# FLC100_remote_v2.net
KiCad netlist of a schematic drawn in EAGLE
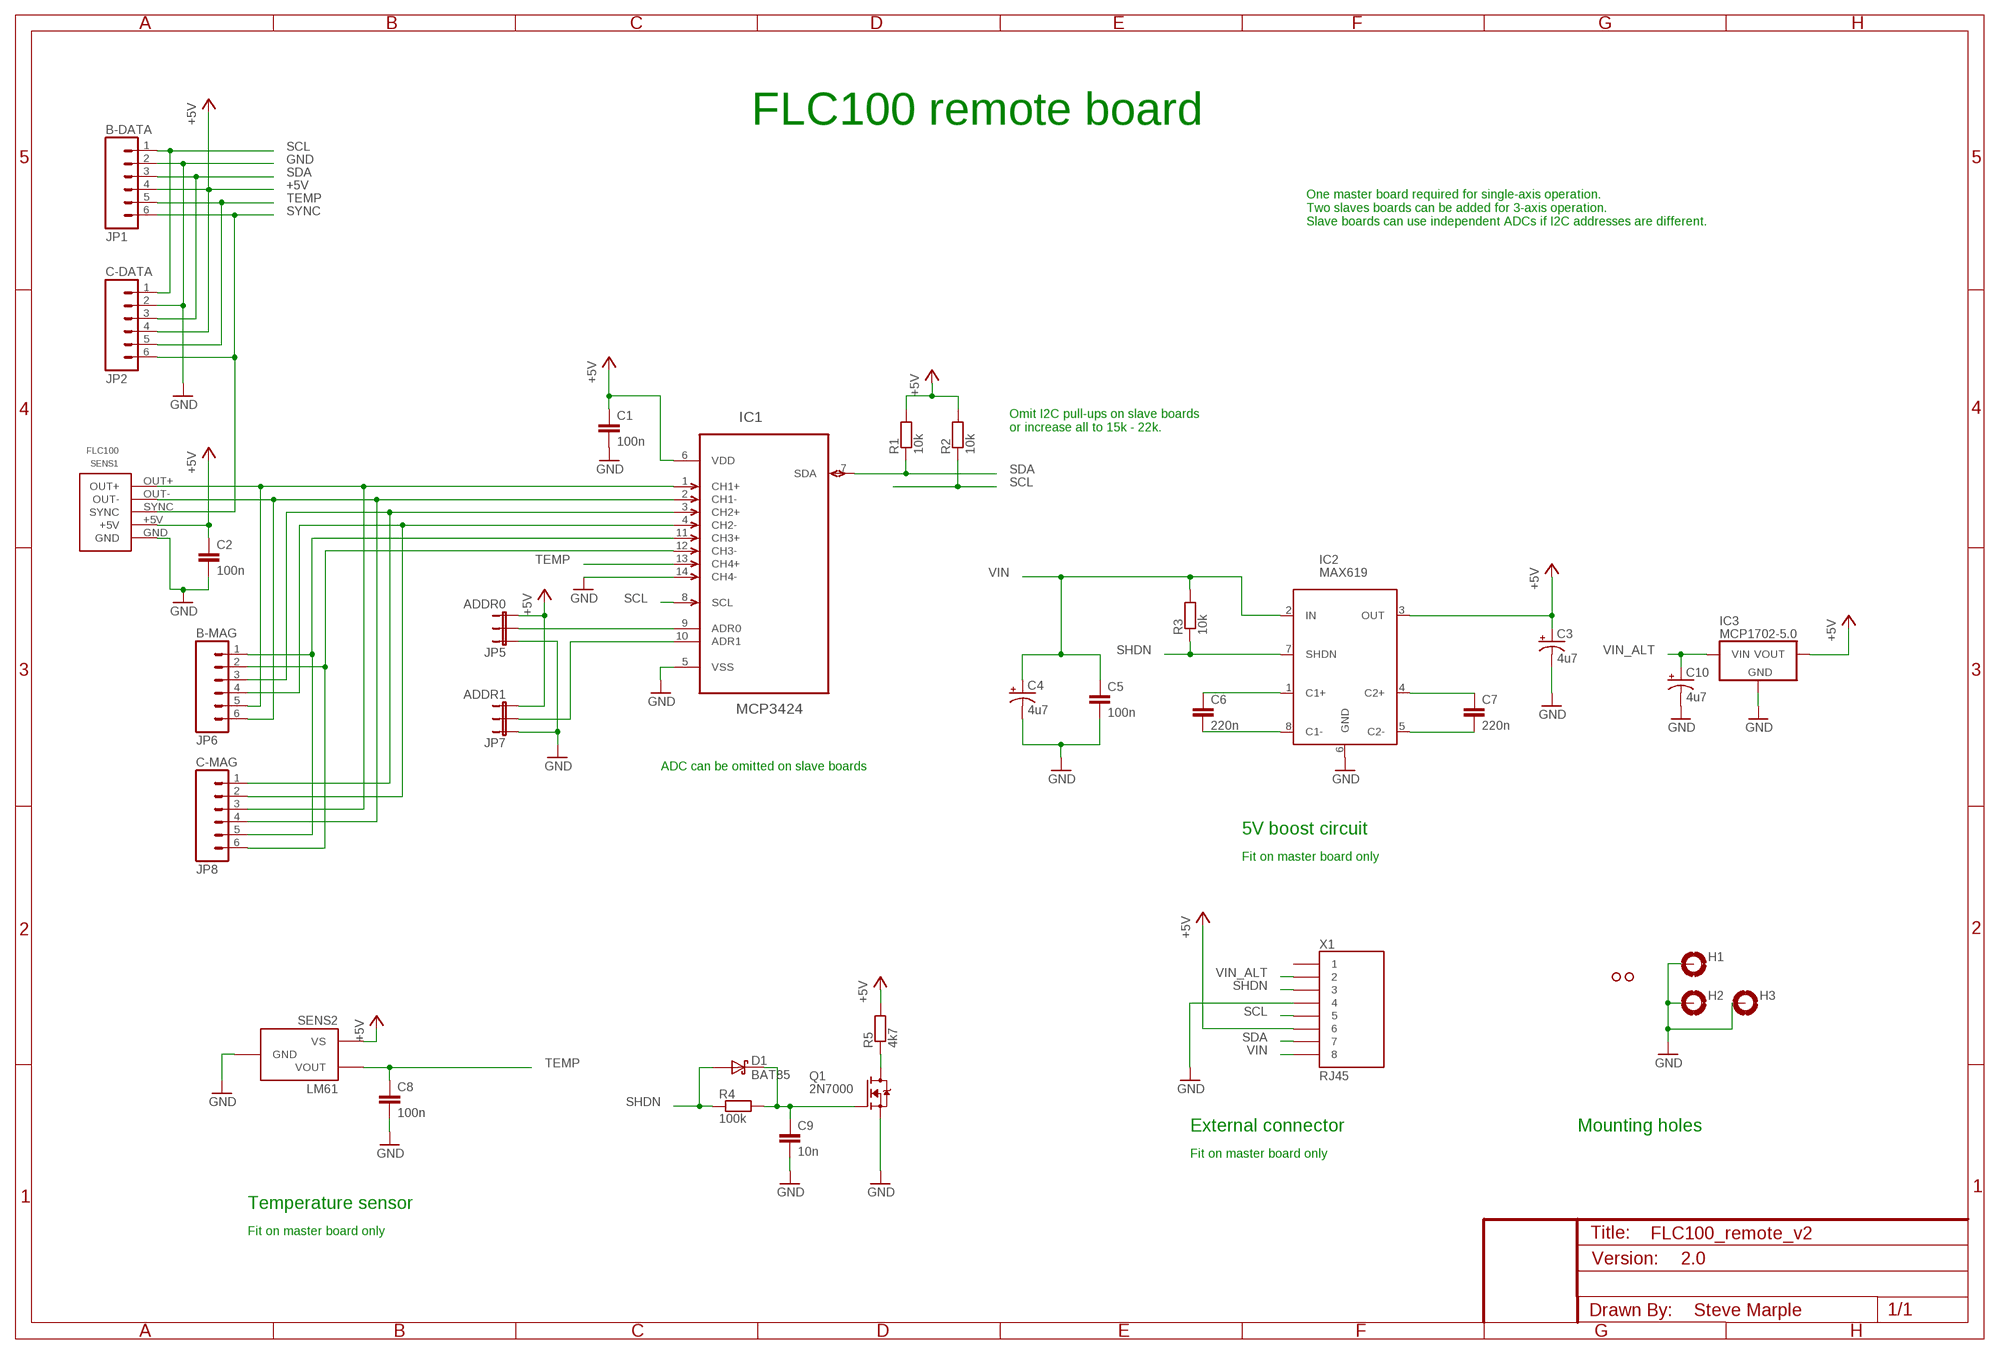
[diagram p0: schematic, sheet 1]

(export (version "E")
  (design (tool "Eeschema 10.0.6"))
  (components
    (comp (ref "C1")
      (value "100n")
      (footprint "eagle-import:CAP-PTH-SMALL")
      (libsource (lib "eagle-import") (part "CAPPTH"))
    )
    (comp (ref "C2")
      (value "100n")
      (footprint "eagle-import:CAP-PTH-SMALL")
      (libsource (lib "eagle-import") (part "CAPPTH"))
    )
    (comp (ref "C3")
      (value "4u7")
      (footprint "eagle-import:CPOL-RADIAL-10UF-25V")
      (libsource (lib "eagle-import") (part "CAP_POLPTH2"))
    )
    (comp (ref "C4")
      (value "4u7")
      (footprint "eagle-import:CPOL-RADIAL-10UF-25V")
      (libsource (lib "eagle-import") (part "CAP_POLPTH2"))
    )
    (comp (ref "C5")
      (value "100n")
      (footprint "eagle-import:CAP-PTH-SMALL")
      (libsource (lib "eagle-import") (part "CAPPTH"))
    )
    (comp (ref "C6")
      (value "220n")
      (footprint "eagle-import:CAP-PTH-SMALL")
      (fields (field (name "MANUFACTURER") "Multicomp") (field (name "PART_NO") "MCRR25221COGJ0100"))
      (libsource (lib "eagle-import") (part "CAPPTH"))
    )
    (comp (ref "C7")
      (value "220n")
      (footprint "eagle-import:CAP-PTH-SMALL")
      (fields (field (name "MANUFACTURER") "Multicomp") (field (name "PART_NO") "MCRR25221COGJ0100"))
      (libsource (lib "eagle-import") (part "CAPPTH"))
    )
    (comp (ref "C8")
      (value "100n")
      (footprint "eagle-import:CAP-PTH-SMALL")
      (libsource (lib "eagle-import") (part "CAPPTH"))
    )
    (comp (ref "C9")
      (value "10n")
      (footprint "eagle-import:CAP-PTH-SMALL")
      (libsource (lib "eagle-import") (part "CAPPTH"))
    )
    (comp (ref "C10")
      (value "4u7")
      (footprint "eagle-import:CPOL-RADIAL-10UF-25V")
      (libsource (lib "eagle-import") (part "CAP_POLPTH2"))
    )
    (comp (ref "D1")
      (value "BAT85")
      (footprint "eagle-import:DIODE-TH-0.4")
      (libsource (lib "eagle-import") (part "DIODE-SCHOTTKY"))
    )
    (comp (ref "H1")
      (value "MOUNT-PAD-ROUND3.0")
      (footprint "eagle-import:3,0-PAD")
      (libsource (lib "eagle-import") (part "MOUNT-PAD-ROUND3.0"))
    )
    (comp (ref "H2")
      (value "MOUNT-PAD-ROUND3.0")
      (footprint "eagle-import:3,0-PAD")
      (libsource (lib "eagle-import") (part "MOUNT-PAD-ROUND3.0"))
    )
    (comp (ref "H3")
      (value "MOUNT-PAD-ROUND3.0")
      (footprint "eagle-import:3,0-PAD")
      (libsource (lib "eagle-import") (part "MOUNT-PAD-ROUND3.0"))
    )
    (comp (ref "IC1")
      (value "MCP3424")
      (footprint "eagle-import:SO14")
      (libsource (lib "eagle-import") (part "MCP3424-E/SLSO14"))
    )
    (comp (ref "IC2")
      (value "MAX619")
      (footprint "eagle-import:SO08")
      (libsource (lib "eagle-import") (part "MAX619SOIC8"))
    )
    (comp (ref "IC3")
      (value "MCP1702-5.0")
      (footprint "eagle-import:TO-92")
      (libsource (lib "eagle-import") (part "MCP1702"))
    )
    (comp (ref "JP1")
      (value "B-DATA")
      (footprint "eagle-import:1X06_FEMALE")
      (libsource (lib "eagle-import") (part "M06FEMALE"))
    )
    (comp (ref "JP2")
      (value "C-DATA")
      (footprint "eagle-import:1X06_FEMALE")
      (libsource (lib "eagle-import") (part "M06FEMALE"))
    )
    (comp (ref "JP5")
      (value "ADDR0")
      (footprint "eagle-import:1X03")
      (libsource (lib "eagle-import") (part "JUMPER-3PTH"))
    )
    (comp (ref "JP6")
      (value "B-MAG")
      (footprint "eagle-import:1X06_FEMALE")
      (libsource (lib "eagle-import") (part "M06FEMALE"))
    )
    (comp (ref "JP7")
      (value "ADDR1")
      (footprint "eagle-import:1X03")
      (libsource (lib "eagle-import") (part "JUMPER-3PTH"))
    )
    (comp (ref "JP8")
      (value "C-MAG")
      (footprint "eagle-import:1X06_FEMALE")
      (libsource (lib "eagle-import") (part "M06FEMALE"))
    )
    (comp (ref "Q1")
      (value "2N7000")
      (footprint "eagle-import:TO-92")
      (libsource (lib "eagle-import") (part "2N7000"))
    )
    (comp (ref "R1")
      (value "10k")
      (footprint "eagle-import:RES-AXIAL-0.4")
      (libsource (lib "eagle-import") (part "RESISTOR"))
    )
    (comp (ref "R2")
      (value "10k")
      (footprint "eagle-import:RES-AXIAL-0.4")
      (libsource (lib "eagle-import") (part "RESISTOR"))
    )
    (comp (ref "R3")
      (value "10k")
      (footprint "eagle-import:RES-AXIAL-0.4")
      (libsource (lib "eagle-import") (part "RESISTOR"))
    )
    (comp (ref "R4")
      (value "100k")
      (footprint "eagle-import:RES-AXIAL-0.4")
      (libsource (lib "eagle-import") (part "RESISTOR"))
    )
    (comp (ref "R5")
      (value "4k7")
      (footprint "eagle-import:RES-AXIAL-0.4")
      (libsource (lib "eagle-import") (part "RESISTOR"))
    )
    (comp (ref "SENS1")
      (value "FLC100")
      (footprint "eagle-import:FLC100")
      (libsource (lib "eagle-import") (part "FLC100"))
    )
    (comp (ref "SENS2")
      (value "LM61")
      (footprint "eagle-import:TO-92")
      (libsource (lib "eagle-import") (part "LM61"))
    )
    (comp (ref "U$1")
      (value "PAD")
      (footprint "eagle-import:PAD")
      (libsource (lib "eagle-import") (part "PAD"))
    )
    (comp (ref "U$2")
      (value "PAD")
      (footprint "eagle-import:PAD")
      (libsource (lib "eagle-import") (part "PAD"))
    )
    (comp (ref "X1")
      (value "RJ45")
      (footprint "eagle-import:RJ45-8")
      (libsource (lib "eagle-import") (part "RJ45-8PTH"))
    )
  )
  (nets
    (net (code "1") (name "+5V") (class "Default")
      (node (ref "C1") (pin "1") (pinfunction "1_1") (pintype "passive"))
      (node (ref "C2") (pin "1") (pinfunction "1_1") (pintype "passive"))
      (node (ref "C3") (pin "1") (pinfunction "+_1") (pintype "passive"))
      (node (ref "IC1") (pin "6") (pinfunction "VDD_6") (pintype "power_in"))
      (node (ref "IC2") (pin "3") (pinfunction "OUT_3") (pintype "power_in"))
      (node (ref "IC3") (pin "3") (pinfunction "VOUT_3") (pintype "passive"))
      (node (ref "JP1") (pin "4") (pinfunction "4_4") (pintype "passive"))
      (node (ref "JP2") (pin "4") (pinfunction "4_4") (pintype "passive"))
      (node (ref "JP5") (pin "3") (pinfunction "3_3") (pintype "passive"))
      (node (ref "JP7") (pin "3") (pinfunction "3_3") (pintype "passive"))
      (node (ref "R1") (pin "P$2") (pinfunction "2_P$2") (pintype "passive"))
      (node (ref "R2") (pin "P$2") (pinfunction "2_P$2") (pintype "passive"))
      (node (ref "R5") (pin "P$2") (pinfunction "2_P$2") (pintype "passive"))
      (node (ref "SENS1") (pin "+5V") (pinfunction "+5V_+5V") (pintype "power_in"))
      (node (ref "SENS2") (pin "1") (pinfunction "VS_1") (pintype "bidirectional"))
      (node (ref "X1") (pin "6") (pinfunction "6_6") (pintype "bidirectional"))
    )
    (net (code "2") (name "/SCL") (class "Default")
      (node (ref "IC1") (pin "8") (pinfunction "SCL_8") (pintype "input"))
      (node (ref "JP1") (pin "1") (pinfunction "1_1") (pintype "passive"))
      (node (ref "JP2") (pin "1") (pinfunction "1_1") (pintype "passive"))
      (node (ref "R2") (pin "P$1") (pinfunction "1_P$1") (pintype "passive"))
      (node (ref "X1") (pin "5") (pinfunction "5_5") (pintype "bidirectional"))
    )
    (net (code "3") (name "/SDA") (class "Default")
      (node (ref "IC1") (pin "7") (pinfunction "SDA_7") (pintype "bidirectional"))
      (node (ref "JP1") (pin "3") (pinfunction "3_3") (pintype "passive"))
      (node (ref "JP2") (pin "3") (pinfunction "3_3") (pintype "passive"))
      (node (ref "R1") (pin "P$1") (pinfunction "1_P$1") (pintype "passive"))
      (node (ref "X1") (pin "7") (pinfunction "7_7") (pintype "bidirectional"))
    )
    (net (code "4") (name "/SHDN") (class "Default")
      (node (ref "D1") (pin "A") (pinfunction "A_A") (pintype "passive"))
      (node (ref "IC2") (pin "7") (pinfunction "SHDN_7") (pintype "input"))
      (node (ref "R3") (pin "P$1") (pinfunction "1_P$1") (pintype "passive"))
      (node (ref "R4") (pin "P$1") (pinfunction "1_P$1") (pintype "passive"))
      (node (ref "X1") (pin "3") (pinfunction "3_3") (pintype "bidirectional"))
    )
    (net (code "5") (name "/SYNC") (class "Default")
      (node (ref "JP1") (pin "6") (pinfunction "6_6") (pintype "passive"))
      (node (ref "JP2") (pin "6") (pinfunction "6_6") (pintype "passive"))
      (node (ref "SENS1") (pin "SYNC") (pinfunction "SYNC_SYNC") (pintype "bidirectional"))
    )
    (net (code "6") (name "/TEMP") (class "Default")
      (node (ref "C8") (pin "1") (pinfunction "1_1") (pintype "passive"))
      (node (ref "IC1") (pin "13") (pinfunction "CH4+_13") (pintype "input"))
      (node (ref "JP1") (pin "5") (pinfunction "5_5") (pintype "passive"))
      (node (ref "JP2") (pin "5") (pinfunction "5_5") (pintype "passive"))
      (node (ref "SENS2") (pin "2") (pinfunction "VOUT_2") (pintype "bidirectional"))
    )
    (net (code "7") (name "/VIN") (class "Default")
      (node (ref "C4") (pin "1") (pinfunction "+_1") (pintype "passive"))
      (node (ref "C5") (pin "1") (pinfunction "1_1") (pintype "passive"))
      (node (ref "IC2") (pin "2") (pinfunction "IN_2") (pintype "power_in"))
      (node (ref "R3") (pin "P$2") (pinfunction "2_P$2") (pintype "passive"))
      (node (ref "X1") (pin "8") (pinfunction "8_8") (pintype "bidirectional"))
    )
    (net (code "8") (name "/VIN_ALT") (class "Default")
      (node (ref "C10") (pin "1") (pinfunction "+_1") (pintype "passive"))
      (node (ref "IC3") (pin "2") (pinfunction "VIN_2") (pintype "input"))
      (node (ref "X1") (pin "2") (pinfunction "2_2") (pintype "bidirectional"))
    )
    (net (code "9") (name "GND") (class "Default")
      (node (ref "C1") (pin "2") (pinfunction "2_2") (pintype "passive"))
      (node (ref "C10") (pin "2") (pinfunction "-_2") (pintype "passive"))
      (node (ref "C2") (pin "2") (pinfunction "2_2") (pintype "passive"))
      (node (ref "C3") (pin "2") (pinfunction "-_2") (pintype "passive"))
      (node (ref "C4") (pin "2") (pinfunction "-_2") (pintype "passive"))
      (node (ref "C5") (pin "2") (pinfunction "2_2") (pintype "passive"))
      (node (ref "C8") (pin "2") (pinfunction "2_2") (pintype "passive"))
      (node (ref "C9") (pin "2") (pinfunction "2_2") (pintype "passive"))
      (node (ref "H1") (pin "B3,0") (pinfunction "MOUNT_B3,0") (pintype "passive"))
      (node (ref "H2") (pin "B3,0") (pinfunction "MOUNT_B3,0") (pintype "passive"))
      (node (ref "H3") (pin "B3,0") (pinfunction "MOUNT_B3,0") (pintype "passive"))
      (node (ref "IC1") (pin "14") (pinfunction "CH4-_14") (pintype "input"))
      (node (ref "IC1") (pin "5") (pinfunction "VSS_5") (pintype "power_in"))
      (node (ref "IC2") (pin "6") (pinfunction "GND_6") (pintype "power_in"))
      (node (ref "IC3") (pin "1") (pinfunction "GND_1") (pintype "passive"))
      (node (ref "JP1") (pin "2") (pinfunction "2_2") (pintype "passive"))
      (node (ref "JP2") (pin "2") (pinfunction "2_2") (pintype "passive"))
      (node (ref "JP5") (pin "1") (pinfunction "1_1") (pintype "passive"))
      (node (ref "JP7") (pin "1") (pinfunction "1_1") (pintype "passive"))
      (node (ref "Q1") (pin "1") (pinfunction "S_1") (pintype "passive"))
      (node (ref "SENS1") (pin "GND") (pinfunction "GND_GND") (pintype "power_in"))
      (node (ref "SENS2") (pin "3") (pinfunction "GND_3") (pintype "bidirectional"))
      (node (ref "X1") (pin "4") (pinfunction "4_4") (pintype "bidirectional"))
    )
    (net (code "10") (name "Net-(IC1-ADR0)") (class "Default")
      (node (ref "IC1") (pin "9") (pinfunction "ADR0_9") (pintype "input"))
      (node (ref "JP5") (pin "2") (pinfunction "2_2") (pintype "passive"))
    )
    (net (code "11") (name "Net-(IC1-ADR1)") (class "Default")
      (node (ref "IC1") (pin "10") (pinfunction "ADR1_10") (pintype "input"))
      (node (ref "JP7") (pin "2") (pinfunction "2_2") (pintype "passive"))
    )
    (net (code "12") (name "Net-(IC1-CH1+)") (class "Default")
      (node (ref "IC1") (pin "1") (pinfunction "CH1+_1") (pintype "input"))
      (node (ref "JP6") (pin "5") (pinfunction "5_5") (pintype "passive"))
      (node (ref "JP8") (pin "3") (pinfunction "3_3") (pintype "passive"))
      (node (ref "SENS1") (pin "OUT+") (pinfunction "OUT+_OUT+") (pintype "output"))
    )
    (net (code "13") (name "Net-(IC1-CH1-)") (class "Default")
      (node (ref "IC1") (pin "2") (pinfunction "CH1-_2") (pintype "input"))
      (node (ref "JP6") (pin "6") (pinfunction "6_6") (pintype "passive"))
      (node (ref "JP8") (pin "4") (pinfunction "4_4") (pintype "passive"))
      (node (ref "SENS1") (pin "OUT-") (pinfunction "OUT-_OUT-") (pintype "output"))
    )
    (net (code "14") (name "Net-(IC1-CH2+)") (class "Default")
      (node (ref "IC1") (pin "3") (pinfunction "CH2+_3") (pintype "input"))
      (node (ref "JP6") (pin "3") (pinfunction "3_3") (pintype "passive"))
      (node (ref "JP8") (pin "1") (pinfunction "1_1") (pintype "passive"))
    )
    (net (code "15") (name "Net-(IC1-CH2-)") (class "Default")
      (node (ref "IC1") (pin "4") (pinfunction "CH2-_4") (pintype "input"))
      (node (ref "JP6") (pin "4") (pinfunction "4_4") (pintype "passive"))
      (node (ref "JP8") (pin "2") (pinfunction "2_2") (pintype "passive"))
    )
    (net (code "16") (name "Net-(IC1-CH3+)") (class "Default")
      (node (ref "IC1") (pin "11") (pinfunction "CH3+_11") (pintype "input"))
      (node (ref "JP6") (pin "1") (pinfunction "1_1") (pintype "passive"))
      (node (ref "JP8") (pin "5") (pinfunction "5_5") (pintype "passive"))
    )
    (net (code "17") (name "Net-(IC1-CH3-)") (class "Default")
      (node (ref "IC1") (pin "12") (pinfunction "CH3-_12") (pintype "input"))
      (node (ref "JP6") (pin "2") (pinfunction "2_2") (pintype "passive"))
      (node (ref "JP8") (pin "6") (pinfunction "6_6") (pintype "passive"))
    )
    (net (code "18") (name "Net-(IC2-C1+)") (class "Default")
      (node (ref "C6") (pin "1") (pinfunction "1_1") (pintype "passive"))
      (node (ref "IC2") (pin "1") (pinfunction "C1+_1") (pintype "bidirectional"))
    )
    (net (code "19") (name "Net-(IC2-C1-)") (class "Default")
      (node (ref "C6") (pin "2") (pinfunction "2_2") (pintype "passive"))
      (node (ref "IC2") (pin "8") (pinfunction "C1-_8") (pintype "bidirectional"))
    )
    (net (code "20") (name "Net-(IC2-C2+)") (class "Default")
      (node (ref "C7") (pin "1") (pinfunction "1_1") (pintype "passive"))
      (node (ref "IC2") (pin "4") (pinfunction "C2+_4") (pintype "bidirectional"))
    )
    (net (code "21") (name "Net-(IC2-C2-)") (class "Default")
      (node (ref "C7") (pin "2") (pinfunction "2_2") (pintype "passive"))
      (node (ref "IC2") (pin "5") (pinfunction "C2-_5") (pintype "bidirectional"))
    )
    (net (code "22") (name "Net-(Q1-D)") (class "Default")
      (node (ref "Q1") (pin "3") (pinfunction "D_3") (pintype "passive"))
      (node (ref "R5") (pin "P$1") (pinfunction "1_P$1") (pintype "passive"))
    )
    (net (code "23") (name "Net-(Q1-G)") (class "Default")
      (node (ref "C9") (pin "1") (pinfunction "1_1") (pintype "passive"))
      (node (ref "D1") (pin "C") (pinfunction "C_C") (pintype "passive"))
      (node (ref "Q1") (pin "2") (pinfunction "G_2") (pintype "passive"))
      (node (ref "R4") (pin "P$2") (pinfunction "2_P$2") (pintype "passive"))
    )
    (net (code "24") (name "unconnected-(U$1-Pad1)") (class "Default")
      (node (ref "U$1") (pin "1") (pinfunction "1_1") (pintype "bidirectional"))
    )
    (net (code "25") (name "unconnected-(U$2-Pad1)") (class "Default")
      (node (ref "U$2") (pin "1") (pinfunction "1_1") (pintype "bidirectional"))
    )
    (net (code "26") (name "unconnected-(X1-Pad1)") (class "Default")
      (node (ref "X1") (pin "1") (pinfunction "1_1") (pintype "bidirectional"))
    )
  )
)
